# StepperDriver.net
KiCad netlist of a schematic drawn in Altium Designer
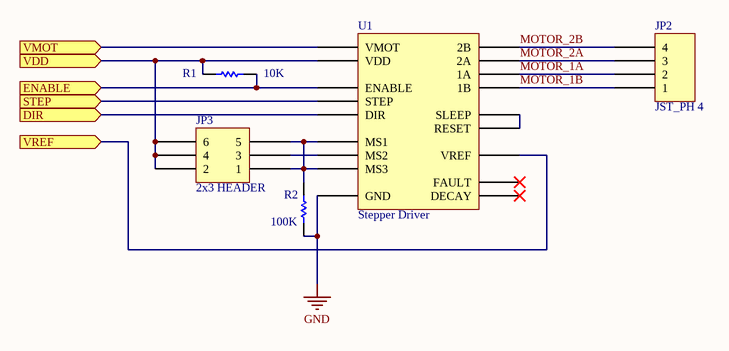
[diagram p0: StepperDriver.SchDoc]

(export (version "E")
  (design (tool "Eeschema 10.0.6"))
  (components
    (comp (ref "JP2") (value "JST_PH 4") (footprint "JST_PH 4") (libsource (lib "Header") (part "JST_PH 4")))
    (comp (ref "JP3")
      (value "2x3 HEADER")
      (footprint "2x3 HEADER")
      (libsource (lib "Header") (part "2x3 HEADER"))
    )
    (comp (ref "R1")
      (value "10K")
      (footprint "RESC0603(1608)_N")
      (description "10K 0.1W 5% 0603 (1608 Metric)  SMD")
      (fields (field (name "TOLERANCE") "5 %") (field (name "POWER") "0.1 W"))
      (libsource (lib "Altium Content Vault") (part "CMP-1012-00098-1"))
    )
    (comp (ref "R2")
      (value "100K")
      (footprint "RESC0603(1608)_N")
      (description "100K 0.1W 5% 0603 (1608 Metric)  SMD")
      (fields (field (name "TOLERANCE") "5 %") (field (name "POWER") "0.1 W"))
      (libsource (lib "Altium Content Vault") (part "CMP-1012-00122-1"))
    )
    (comp (ref "U1")
      (value "Stepper Driver")
      (footprint "SureStepr")
      (libsource (lib "Components") (part "Stepper Driver"))
    )
  )
  (nets
    (net (code "1") (name "/DIR") (class "Default")
      (node (ref "U1") (pin "DIR") (pinfunction "DIR_DIR") (pintype "passive"))
    )
    (net (code "2") (name "/ENABLE") (class "Default")
      (node (ref "R1") (pin "1") (pinfunction "1_1") (pintype "passive"))
      (node (ref "U1") (pin "ENABLE") (pinfunction "ENABLE_ENABLE") (pintype "passive"))
    )
    (net (code "3") (name "/MOTOR_1A") (class "Default")
      (node (ref "JP2") (pin "2") (pinfunction "2_2") (pintype "passive"))
      (node (ref "U1") (pin "1A") (pinfunction "1A_1A") (pintype "passive"))
    )
    (net (code "4") (name "/MOTOR_1B") (class "Default")
      (node (ref "JP2") (pin "1") (pinfunction "1_1") (pintype "passive"))
      (node (ref "U1") (pin "1B") (pinfunction "1B_1B") (pintype "passive"))
    )
    (net (code "5") (name "/MOTOR_2A") (class "Default")
      (node (ref "JP2") (pin "3") (pinfunction "3_3") (pintype "passive"))
      (node (ref "U1") (pin "2A") (pinfunction "2A_2A") (pintype "passive"))
    )
    (net (code "6") (name "/MOTOR_2B") (class "Default")
      (node (ref "JP2") (pin "4") (pinfunction "4_4") (pintype "passive"))
      (node (ref "U1") (pin "2B") (pinfunction "2B_2B") (pintype "passive"))
    )
    (net (code "7") (name "/STEP") (class "Default")
      (node (ref "U1") (pin "STEP") (pinfunction "STEP_STEP") (pintype "passive"))
    )
    (net (code "8") (name "/VDD") (class "Default")
      (node (ref "JP3") (pin "2") (pinfunction "2_2") (pintype "passive"))
      (node (ref "JP3") (pin "4") (pinfunction "4_4") (pintype "passive"))
      (node (ref "JP3") (pin "6") (pinfunction "6_6") (pintype "passive"))
      (node (ref "R1") (pin "2") (pinfunction "2_2") (pintype "passive"))
      (node (ref "U1") (pin "VDD") (pinfunction "VDD_VDD") (pintype "passive"))
    )
    (net (code "9") (name "/VMOT") (class "Default")
      (node (ref "U1") (pin "VMOT") (pinfunction "VMOT_VMOT") (pintype "passive"))
    )
    (net (code "10") (name "/VREF") (class "Default")
      (node (ref "U1") (pin "VREF") (pinfunction "VREF_VREF") (pintype "passive"))
    )
    (net (code "11") (name "GND") (class "Default")
      (node (ref "R2") (pin "1") (pinfunction "1_1") (pintype "passive"))
      (node (ref "U1") (pin "GND") (pinfunction "GND_GND") (pintype "passive"))
    )
    (net (code "12") (name "Net-(JP3-Pad1)") (class "Default")
      (node (ref "JP3") (pin "1") (pinfunction "1_1") (pintype "passive"))
      (node (ref "JP3") (pin "5") (pinfunction "5_5") (pintype "passive"))
      (node (ref "R2") (pin "2") (pinfunction "2_2") (pintype "passive"))
      (node (ref "U1") (pin "MS1") (pinfunction "MS1_MS1") (pintype "passive"))
      (node (ref "U1") (pin "MS3") (pinfunction "MS3_MS3") (pintype "passive"))
    )
    (net (code "13") (name "Net-(JP3-Pad3)") (class "Default")
      (node (ref "JP3") (pin "3") (pinfunction "3_3") (pintype "passive"))
      (node (ref "U1") (pin "MS2") (pinfunction "MS2_MS2") (pintype "passive"))
    )
    (net (code "14") (name "Net-(U1-PadRESET)") (class "Default")
      (node (ref "U1") (pin "RESET") (pinfunction "RESET_RESET") (pintype "passive"))
      (node (ref "U1") (pin "SLEEP") (pinfunction "SLEEP_SLEEP") (pintype "passive"))
    )
    (net (code "15") (name "unconnected-(U1-PadDECAY)") (class "Default")
      (node (ref "U1") (pin "DECAY") (pinfunction "DECAY_DECAY") (pintype "passive+no_connect"))
    )
    (net (code "16") (name "unconnected-(U1-PadFAULT)") (class "Default")
      (node (ref "U1") (pin "FAULT") (pinfunction "FAULT_FAULT") (pintype "passive+no_connect"))
    )
  )
)
